# System.net
KiCad netlist of a schematic drawn in Altium Designer
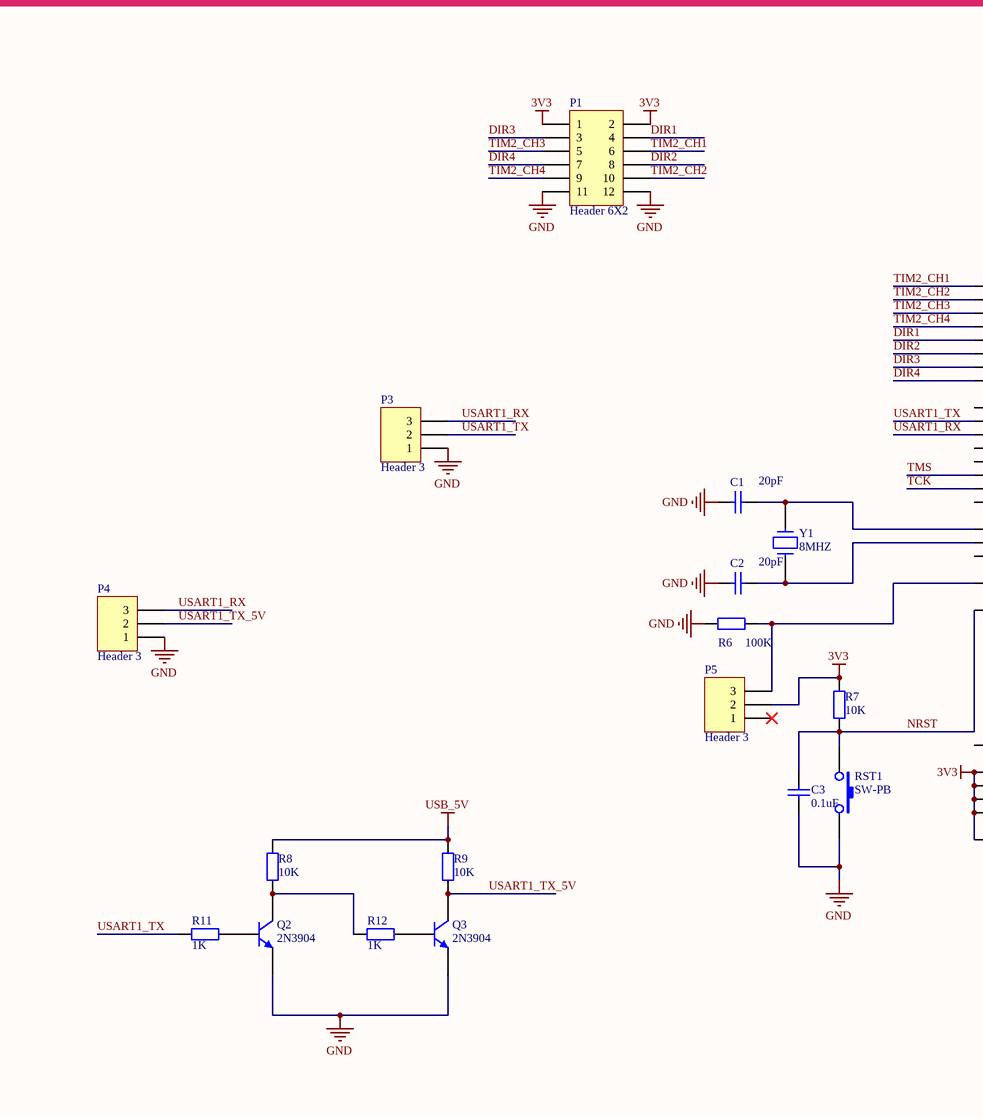
[diagram p0: System.SchDoc, left]
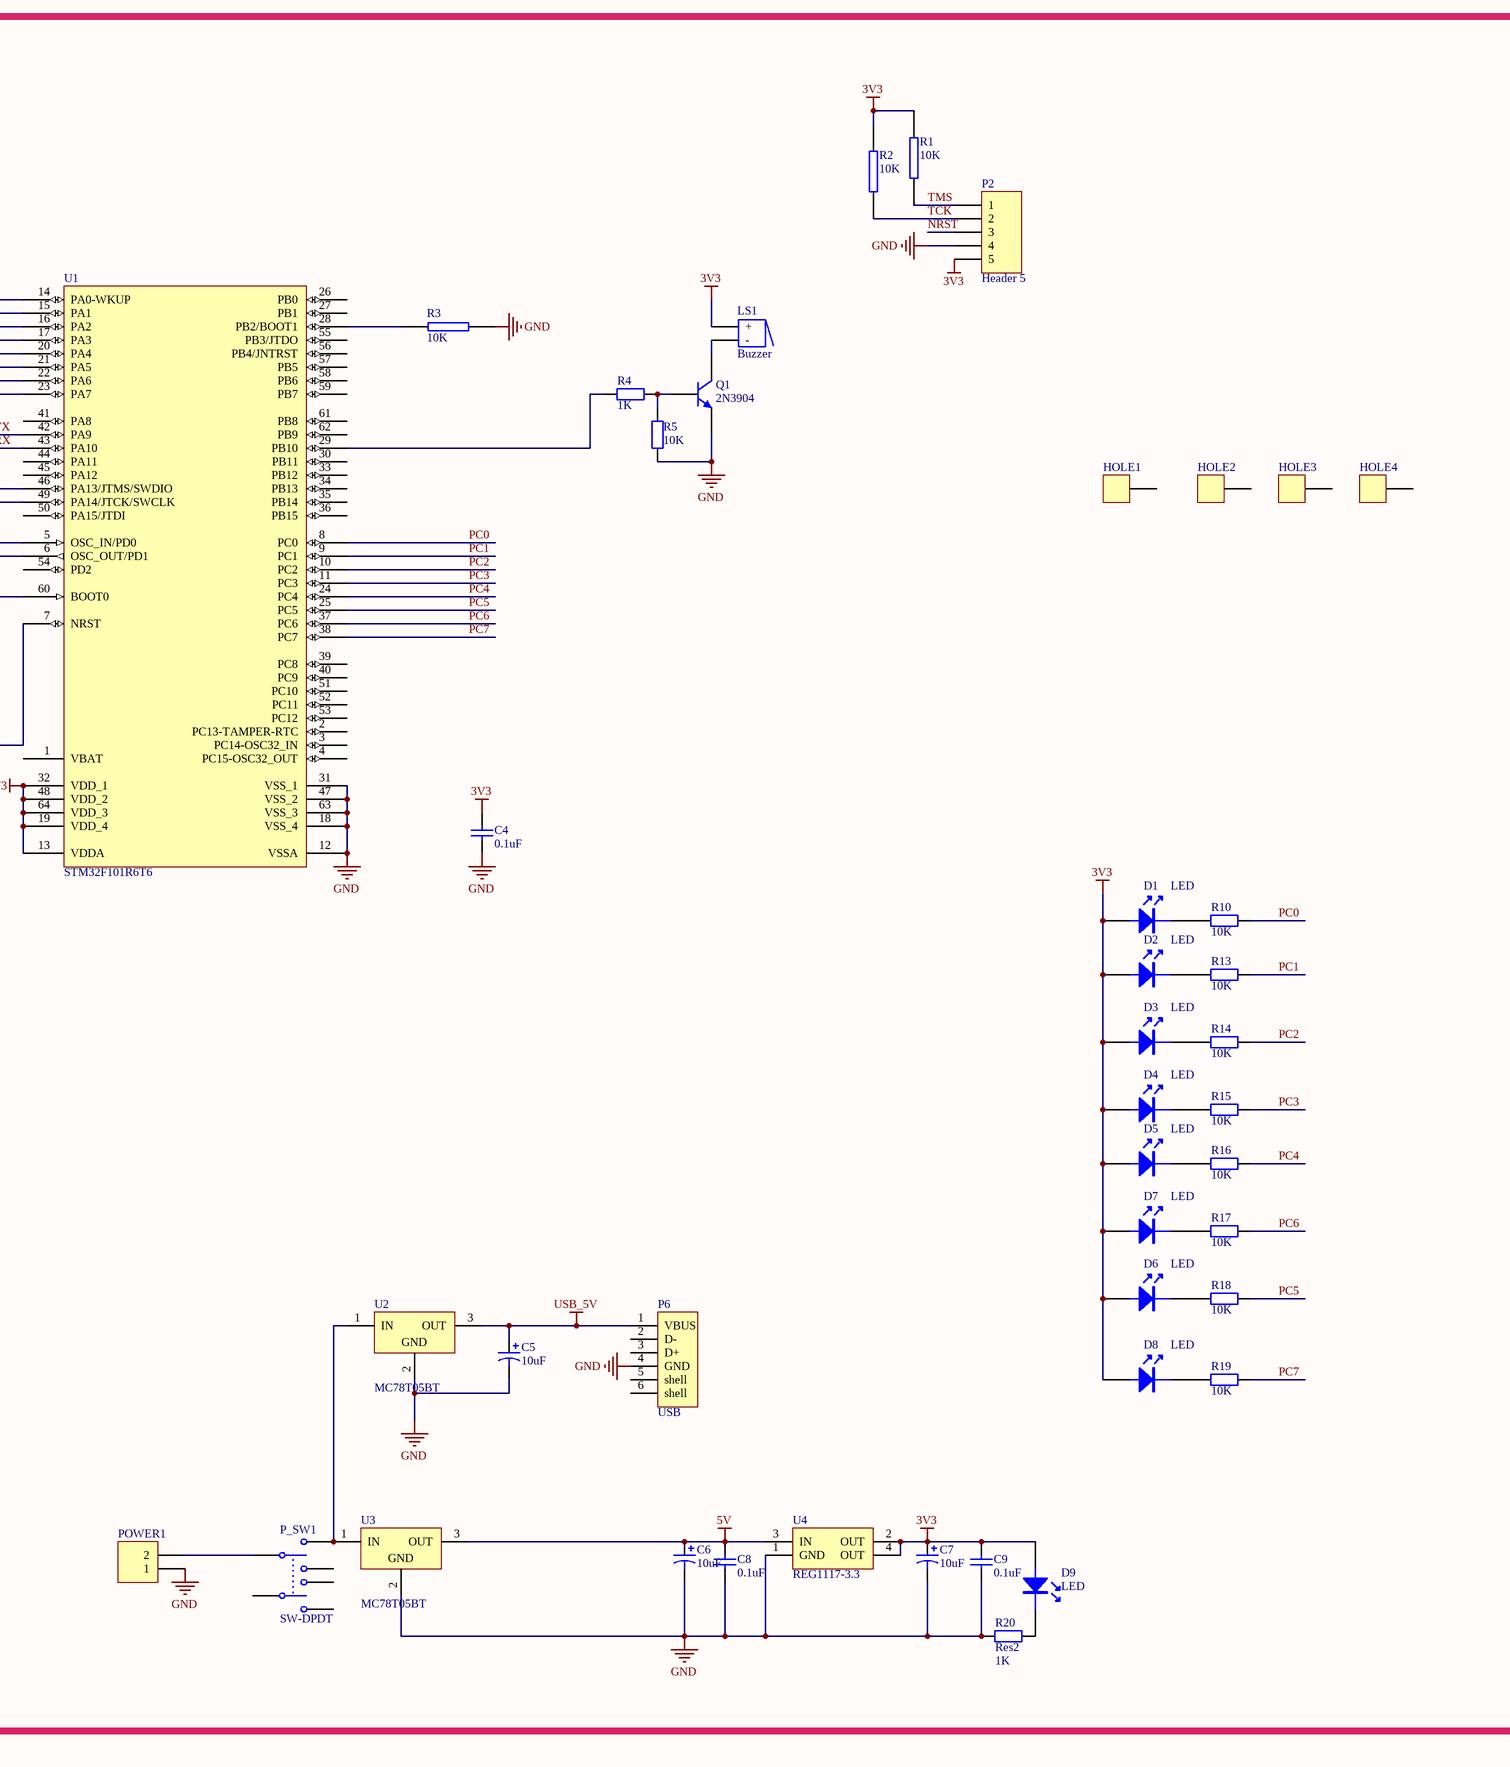
[diagram p1: System.SchDoc, right]

(export (version "E")
  (design (tool "Eeschema 10.0.6"))
  (components
    (comp (ref "C1")
      (value "20pF")
      (footprint "SMDC0805")
      (description "Capacitor")
      (fields (field (name "Comment") "Cap") (field (name "PUBLISHER") "Altium Limited"))
      (libsource (lib "Miscellaneous Devices") (part "Cap"))
    )
    (comp (ref "C2")
      (value "20pF")
      (footprint "SMDC0805")
      (description "Capacitor")
      (fields (field (name "Comment") "Cap") (field (name "PUBLISHER") "Altium Limited"))
      (libsource (lib "Miscellaneous Devices") (part "Cap"))
    )
    (comp (ref "C3")
      (value "0.1uF")
      (footprint "SMDC0805")
      (description "Capacitor")
      (fields (field (name "Comment") "Cap") (field (name "PUBLISHER") "Altium Limited"))
      (libsource (lib "Miscellaneous Devices") (part "Cap"))
    )
    (comp (ref "C4")
      (value "0.1uF")
      (footprint "SMDC0805")
      (description "Capacitor")
      (fields (field (name "Comment") "Cap") (field (name "PUBLISHER") "Altium Limited"))
      (libsource (lib "Miscellaneous Devices") (part "Cap"))
    )
    (comp (ref "C5")
      (value "10uF")
      (footprint "SMDT_C")
      (description "Polarized Capacitor (Radial)")
      (fields (field (name "Comment") "Cap Pol1") (field (name "PUBLISHER") "Altium Limited"))
      (libsource (lib "Miscellaneous Devices") (part "Cap Pol1"))
    )
    (comp (ref "C6")
      (value "10uF")
      (footprint "SMDT_C")
      (description "Polarized Capacitor (Radial)")
      (fields (field (name "Comment") "Cap Pol1") (field (name "PUBLISHER") "Altium Limited"))
      (libsource (lib "Miscellaneous Devices") (part "Cap Pol1"))
    )
    (comp (ref "C7")
      (value "10uF")
      (footprint "SMDT_C")
      (description "Polarized Capacitor (Radial)")
      (fields (field (name "Comment") "Cap Pol1") (field (name "PUBLISHER") "Altium Limited"))
      (libsource (lib "Miscellaneous Devices") (part "Cap Pol1"))
    )
    (comp (ref "C8")
      (value "0.1uF")
      (footprint "SMDC0805")
      (description "Capacitor")
      (fields (field (name "Comment") "Cap") (field (name "PUBLISHER") "Altium Limited"))
      (libsource (lib "Miscellaneous Devices") (part "Cap"))
    )
    (comp (ref "C9")
      (value "0.1uF")
      (footprint "SMDC0805")
      (description "Capacitor")
      (fields (field (name "Comment") "Cap") (field (name "PUBLISHER") "Altium Limited"))
      (libsource (lib "Miscellaneous Devices") (part "Cap"))
    )
    (comp (ref "D1") (value "LED") (footprint "LED_0805") (libsource (lib "library") (part "LED")))
    (comp (ref "D2") (value "LED") (footprint "LED_0805") (libsource (lib "library") (part "LED")))
    (comp (ref "D3") (value "LED") (footprint "LED_0805") (libsource (lib "library") (part "LED")))
    (comp (ref "D4") (value "LED") (footprint "LED_0805") (libsource (lib "library") (part "LED")))
    (comp (ref "D5") (value "LED") (footprint "LED_0805") (libsource (lib "library") (part "LED")))
    (comp (ref "D6") (value "LED") (footprint "LED_0805") (libsource (lib "library") (part "LED")))
    (comp (ref "D7") (value "LED") (footprint "LED_0805") (libsource (lib "library") (part "LED")))
    (comp (ref "D8") (value "LED") (footprint "LED_0805") (libsource (lib "library") (part "LED")))
    (comp (ref "D9") (value "LED") (footprint "LED_0805") (libsource (lib "library") (part "LED")))
    (comp (ref "HOLE1") (value "TP") (footprint "HOLE") (libsource (lib "library") (part "TestPoint")))
    (comp (ref "HOLE2") (value "TP") (footprint "HOLE") (libsource (lib "library") (part "TestPoint")))
    (comp (ref "HOLE3") (value "TP") (footprint "HOLE") (libsource (lib "library") (part "TestPoint")))
    (comp (ref "HOLE4") (value "TP") (footprint "HOLE") (libsource (lib "library") (part "TestPoint")))
    (comp (ref "LS1")
      (value "Buzzer")
      (footprint "Buzzer_min")
      (description "Magnetic Transducer Buzzer")
      (fields (field (name "PUBLISHER") "Altium Limited"))
      (libsource (lib "library") (part "Buzzer"))
    )
    (comp (ref "P1")
      (value "Header 6X2")
      (footprint "HDR2X6")
      (description "Header, 6-Pin, Dual row")
      (fields (field (name "PUBLISHER") "Altium Limited"))
      (libsource (lib "Miscellaneous Connectors") (part "Header 6X2"))
    )
    (comp (ref "P2")
      (value "Header 5")
      (footprint "HDR1X5")
      (description "Header, 5-Pin")
      (fields (field (name "PUBLISHER") "Altium Limited"))
      (libsource (lib "Miscellaneous Connectors") (part "Header 5"))
    )
    (comp (ref "P3")
      (value "Header 3")
      (footprint "HDR1X3")
      (description "Header, 3-Pin")
      (fields (field (name "PUBLISHER") "Altium Limited"))
      (libsource (lib "Miscellaneous Connectors") (part "Header 3"))
    )
    (comp (ref "P4")
      (value "Header 3")
      (footprint "HDR1X3")
      (description "Header, 3-Pin")
      (fields (field (name "PUBLISHER") "Altium Limited"))
      (libsource (lib "Miscellaneous Connectors") (part "Header 3"))
    )
    (comp (ref "P5")
      (value "Header 3")
      (footprint "HDR1X3")
      (description "Header, 3-Pin")
      (fields (field (name "PUBLISHER") "Altium Limited"))
      (libsource (lib "Miscellaneous Connectors") (part "Header 3"))
    )
    (comp (ref "P6") (value "USB") (footprint "USB-A") (libsource (lib "Lib") (part "USB")))
    (comp (ref "POWER1")
      (value "Header 2")
      (footprint "POW")
      (description "Header, 2-Pin")
      (fields (field (name "PUBLISHER") "Altium Limited"))
      (libsource (lib "Miscellaneous Connectors") (part "Header 2"))
    )
    (comp (ref "P_SW1")
      (value "SW-DPDT")
      (footprint "PW-S")
      (description "Double-Pole, Double-Throw Switch")
      (fields (field (name "PUBLISHER") "Altium Limited"))
      (libsource (lib "Miscellaneous Devices") (part "SW-DPDT"))
    )
    (comp (ref "Q1")
      (value "2N3904")
      (footprint "SOT23")
      (description "NPN General Purpose Amplifier")
      (fields (field (name "PUBLISHER") "Altium Limited"))
      (libsource (lib "library") (part "2N3904"))
    )
    (comp (ref "Q2")
      (value "2N3904")
      (footprint "SOT23")
      (description "NPN General Purpose Amplifier")
      (fields (field (name "PUBLISHER") "Altium Limited"))
      (libsource (lib "library") (part "2N3904"))
    )
    (comp (ref "Q3")
      (value "2N3904")
      (footprint "SOT23")
      (description "NPN General Purpose Amplifier")
      (fields (field (name "PUBLISHER") "Altium Limited"))
      (libsource (lib "library") (part "2N3904"))
    )
    (comp (ref "R1") (value "10K") (footprint "SMDR0805") (libsource (lib "*") (part "RES2")))
    (comp (ref "R2") (value "10K") (footprint "SMDR0805") (libsource (lib "*") (part "RES2")))
    (comp (ref "R3") (value "10K") (footprint "SMDR0805") (libsource (lib "*") (part "RES2")))
    (comp (ref "R4")
      (value "1K")
      (footprint "SMDR0805")
      (description "Resistor")
      (fields (field (name "Comment") "Res2") (field (name "PUBLISHER") "Altium Limited"))
      (libsource (lib "Miscellaneous Devices") (part "Res2"))
    )
    (comp (ref "R5")
      (value "10K")
      (footprint "SMDR0805")
      (description "Resistor")
      (fields (field (name "Comment") "Res2") (field (name "PUBLISHER") "Altium Limited"))
      (libsource (lib "") (part "Res2_2"))
    )
    (comp (ref "R6")
      (value "100K")
      (footprint "SMDR0805")
      (description "Resistor")
      (fields (field (name "Comment") "Res2") (field (name "PUBLISHER") "Altium Limited"))
      (libsource (lib "") (part "Res2_2"))
    )
    (comp (ref "R7")
      (value "10K")
      (footprint "SMDR0805")
      (description "Resistor")
      (fields (field (name "Comment") "Res2") (field (name "PUBLISHER") "Altium Limited"))
      (libsource (lib "Miscellaneous Devices") (part "Res2"))
    )
    (comp (ref "R8")
      (value "10K")
      (footprint "SMDR0805")
      (description "Resistor")
      (fields (field (name "Comment") "Res2") (field (name "PUBLISHER") "Altium Limited"))
      (libsource (lib "") (part "Res2_2"))
    )
    (comp (ref "R9")
      (value "10K")
      (footprint "SMDR0805")
      (description "Resistor")
      (fields (field (name "Comment") "Res2") (field (name "PUBLISHER") "Altium Limited"))
      (libsource (lib "") (part "Res2_2"))
    )
    (comp (ref "R10")
      (value "10K")
      (footprint "SMDR0805")
      (description "Resistor")
      (fields (field (name "Comment") "Res2") (field (name "PUBLISHER") "Altium Limited"))
      (libsource (lib "") (part "Res2_1"))
    )
    (comp (ref "R11")
      (value "1K")
      (footprint "SMDR0805")
      (description "Resistor")
      (fields (field (name "Comment") "Res2") (field (name "PUBLISHER") "Altium Limited"))
      (libsource (lib "Miscellaneous Devices") (part "Res2"))
    )
    (comp (ref "R12")
      (value "1K")
      (footprint "SMDR0805")
      (description "Resistor")
      (fields (field (name "Comment") "Res2") (field (name "PUBLISHER") "Altium Limited"))
      (libsource (lib "Miscellaneous Devices") (part "Res2"))
    )
    (comp (ref "R13")
      (value "10K")
      (footprint "SMDR0805")
      (description "Resistor")
      (fields (field (name "Comment") "Res2") (field (name "PUBLISHER") "Altium Limited"))
      (libsource (lib "") (part "Res2_1"))
    )
    (comp (ref "R14")
      (value "10K")
      (footprint "SMDR0805")
      (description "Resistor")
      (fields (field (name "Comment") "Res2") (field (name "PUBLISHER") "Altium Limited"))
      (libsource (lib "") (part "Res2_1"))
    )
    (comp (ref "R15")
      (value "10K")
      (footprint "SMDR0805")
      (description "Resistor")
      (fields (field (name "Comment") "Res2") (field (name "PUBLISHER") "Altium Limited"))
      (libsource (lib "") (part "Res2_1"))
    )
    (comp (ref "R16")
      (value "10K")
      (footprint "SMDR0805")
      (description "Resistor")
      (fields (field (name "Comment") "Res2") (field (name "PUBLISHER") "Altium Limited"))
      (libsource (lib "") (part "Res2_1"))
    )
    (comp (ref "R17")
      (value "10K")
      (footprint "SMDR0805")
      (description "Resistor")
      (fields (field (name "Comment") "Res2") (field (name "PUBLISHER") "Altium Limited"))
      (libsource (lib "") (part "Res2_1"))
    )
    (comp (ref "R18")
      (value "10K")
      (footprint "SMDR0805")
      (description "Resistor")
      (fields (field (name "Comment") "Res2") (field (name "PUBLISHER") "Altium Limited"))
      (libsource (lib "") (part "Res2_1"))
    )
    (comp (ref "R19")
      (value "10K")
      (footprint "SMDR0805")
      (description "Resistor")
      (fields (field (name "Comment") "Res2") (field (name "PUBLISHER") "Altium Limited"))
      (libsource (lib "") (part "Res2_1"))
    )
    (comp (ref "R20")
      (value "Res2")
      (footprint "SMDR0805")
      (description "Resistor")
      (fields (field (name "ALTIUM_VALUE") "1K") (field (name "PUBLISHER") "Altium Limited"))
      (libsource (lib "") (part "Res2_2"))
    )
    (comp (ref "RST1") (value "SW-PB") (footprint "key_2pin") (libsource (lib "library") (part "SW-PB")))
    (comp (ref "U1")
      (value "STM32F101R6T6")
      (footprint "LQFP64_M")
      (description "STM32 ARM-based 32-bit MCU with 32 Kbytes Flash, 64-pin LQFP, Industrial Temperature")
      (fields (field (name "PUBLISHER") "Altium Limited"))
      (libsource (lib "ST Microcontroller 32-Bit STM32") (part "STM32F101R6T6"))
    )
    (comp (ref "U2")
      (value "MC78T05BT")
      (footprint "MC78M05C")
      (description "Three-Ampere Positive Fixed Voltage Regulator")
      (fields (field (name "PUBLISHER") "Altium Limited"))
      (libsource (lib "Motorola Power Mgt Voltage Regulator") (part "MC78T05BT"))
    )
    (comp (ref "U3")
      (value "MC78T05BT")
      (footprint "MC78M05C")
      (description "Three-Ampere Positive Fixed Voltage Regulator")
      (fields (field (name "PUBLISHER") "Altium Limited"))
      (libsource (lib "Motorola Power Mgt Voltage Regulator") (part "MC78T05BT"))
    )
    (comp (ref "U4")
      (value "REG1117-3.3")
      (footprint "SOT-23")
      (description "800mA and 1A Low Dropout Positive Regulator 2.85V, 3.3V, 5V, and Adjustable")
      (fields (field (name "PUBLISHER") "*"))
      (libsource (lib "library") (part "REG1117-3.3"))
    )
    (comp (ref "Y1")
      (value "8MHZ")
      (footprint "可换晶振")
      (description "Crystal")
      (libsource (lib "library") (part "CRYSTAL"))
    )
  )
  (nets
    (net (code "1") (name "/DIR1") (class "Default")
      (node (ref "P1") (pin "4") (pinfunction "4_4") (pintype "passive"))
      (node (ref "U1") (pin "20") (pinfunction "PA4_20") (pintype "bidirectional"))
    )
    (net (code "2") (name "/DIR2") (class "Default")
      (node (ref "P1") (pin "8") (pinfunction "8_8") (pintype "passive"))
      (node (ref "U1") (pin "21") (pinfunction "PA5_21") (pintype "bidirectional"))
    )
    (net (code "3") (name "/DIR3") (class "Default")
      (node (ref "P1") (pin "3") (pinfunction "3_3") (pintype "passive"))
      (node (ref "U1") (pin "22") (pinfunction "PA6_22") (pintype "bidirectional"))
    )
    (net (code "4") (name "/DIR4") (class "Default")
      (node (ref "P1") (pin "7") (pinfunction "7_7") (pintype "passive"))
      (node (ref "U1") (pin "23") (pinfunction "PA7_23") (pintype "bidirectional"))
    )
    (net (code "5") (name "/NRST") (class "Default")
      (node (ref "C3") (pin "2") (pinfunction "2_2") (pintype "passive"))
      (node (ref "P2") (pin "3") (pinfunction "3_3") (pintype "passive"))
      (node (ref "R7") (pin "1") (pinfunction "1_1") (pintype "passive"))
      (node (ref "RST1") (pin "1") (pinfunction "1_1") (pintype "passive"))
      (node (ref "U1") (pin "7") (pinfunction "NRST_7") (pintype "bidirectional"))
    )
    (net (code "6") (name "/PC0") (class "Default")
      (node (ref "R10") (pin "1") (pinfunction "1_1") (pintype "passive"))
      (node (ref "U1") (pin "8") (pinfunction "PC0_8") (pintype "bidirectional"))
    )
    (net (code "7") (name "/PC1") (class "Default")
      (node (ref "R13") (pin "1") (pinfunction "1_1") (pintype "passive"))
      (node (ref "U1") (pin "9") (pinfunction "PC1_9") (pintype "bidirectional"))
    )
    (net (code "8") (name "/PC2") (class "Default")
      (node (ref "R14") (pin "1") (pinfunction "1_1") (pintype "passive"))
      (node (ref "U1") (pin "10") (pinfunction "PC2_10") (pintype "bidirectional"))
    )
    (net (code "9") (name "/PC3") (class "Default")
      (node (ref "R15") (pin "1") (pinfunction "1_1") (pintype "passive"))
      (node (ref "U1") (pin "11") (pinfunction "PC3_11") (pintype "bidirectional"))
    )
    (net (code "10") (name "/PC4") (class "Default")
      (node (ref "R16") (pin "1") (pinfunction "1_1") (pintype "passive"))
      (node (ref "U1") (pin "24") (pinfunction "PC4_24") (pintype "bidirectional"))
    )
    (net (code "11") (name "/PC5") (class "Default")
      (node (ref "R18") (pin "1") (pinfunction "1_1") (pintype "passive"))
      (node (ref "U1") (pin "25") (pinfunction "PC5_25") (pintype "bidirectional"))
    )
    (net (code "12") (name "/PC6") (class "Default")
      (node (ref "R17") (pin "1") (pinfunction "1_1") (pintype "passive"))
      (node (ref "U1") (pin "37") (pinfunction "PC6_37") (pintype "bidirectional"))
    )
    (net (code "13") (name "/PC7") (class "Default")
      (node (ref "R19") (pin "1") (pinfunction "1_1") (pintype "passive"))
      (node (ref "U1") (pin "38") (pinfunction "PC7_38") (pintype "bidirectional"))
    )
    (net (code "14") (name "/TCK") (class "Default")
      (node (ref "P2") (pin "2") (pinfunction "2_2") (pintype "passive"))
      (node (ref "R2") (pin "2") (pinfunction "2_2") (pintype "passive"))
      (node (ref "U1") (pin "49") (pinfunction "PA14/JTCK/SWCLK_49") (pintype "bidirectional"))
    )
    (net (code "15") (name "/TIM2_CH1") (class "Default")
      (node (ref "P1") (pin "6") (pinfunction "6_6") (pintype "passive"))
      (node (ref "U1") (pin "14") (pinfunction "PA0-WKUP_14") (pintype "bidirectional"))
    )
    (net (code "16") (name "/TIM2_CH2") (class "Default")
      (node (ref "P1") (pin "10") (pinfunction "10_10") (pintype "passive"))
      (node (ref "U1") (pin "15") (pinfunction "PA1_15") (pintype "bidirectional"))
    )
    (net (code "17") (name "/TIM2_CH3") (class "Default")
      (node (ref "P1") (pin "5") (pinfunction "5_5") (pintype "passive"))
      (node (ref "U1") (pin "16") (pinfunction "PA2_16") (pintype "bidirectional"))
    )
    (net (code "18") (name "/TIM2_CH4") (class "Default")
      (node (ref "P1") (pin "9") (pinfunction "9_9") (pintype "passive"))
      (node (ref "U1") (pin "17") (pinfunction "PA3_17") (pintype "bidirectional"))
    )
    (net (code "19") (name "/TMS") (class "Default")
      (node (ref "P2") (pin "1") (pinfunction "1_1") (pintype "passive"))
      (node (ref "R1") (pin "2") (pinfunction "2_2") (pintype "passive"))
      (node (ref "U1") (pin "46") (pinfunction "PA13/JTMS/SWDIO_46") (pintype "bidirectional"))
    )
    (net (code "20") (name "/USART1_RX") (class "Default")
      (node (ref "P3") (pin "3") (pinfunction "3_3") (pintype "passive"))
      (node (ref "P4") (pin "3") (pinfunction "3_3") (pintype "passive"))
      (node (ref "U1") (pin "43") (pinfunction "PA10_43") (pintype "bidirectional"))
    )
    (net (code "21") (name "/USART1_TX") (class "Default")
      (node (ref "P3") (pin "2") (pinfunction "2_2") (pintype "passive"))
      (node (ref "R11") (pin "1") (pinfunction "1_1") (pintype "passive"))
      (node (ref "U1") (pin "42") (pinfunction "PA9_42") (pintype "bidirectional"))
    )
    (net (code "22") (name "/USART1_TX_5V") (class "Default")
      (node (ref "P4") (pin "2") (pinfunction "2_2") (pintype "passive"))
      (node (ref "Q3") (pin "3") (pinfunction "C_3") (pintype "passive"))
      (node (ref "R9") (pin "1") (pinfunction "1_1") (pintype "passive"))
    )
    (net (code "23") (name "3V3") (class "Default")
      (node (ref "C4") (pin "2") (pinfunction "2_2") (pintype "passive"))
      (node (ref "C7") (pin "1") (pinfunction "1_1") (pintype "passive"))
      (node (ref "C9") (pin "2") (pinfunction "2_2") (pintype "passive"))
      (node (ref "D1") (pin "1") (pinfunction "A_1") (pintype "passive"))
      (node (ref "D2") (pin "1") (pinfunction "A_1") (pintype "passive"))
      (node (ref "D3") (pin "1") (pinfunction "A_1") (pintype "passive"))
      (node (ref "D4") (pin "1") (pinfunction "A_1") (pintype "passive"))
      (node (ref "D5") (pin "1") (pinfunction "A_1") (pintype "passive"))
      (node (ref "D6") (pin "1") (pinfunction "A_1") (pintype "passive"))
      (node (ref "D7") (pin "1") (pinfunction "A_1") (pintype "passive"))
      (node (ref "D8") (pin "1") (pinfunction "A_1") (pintype "passive"))
      (node (ref "D9") (pin "1") (pinfunction "A_1") (pintype "passive"))
      (node (ref "LS1") (pin "1") (pinfunction "+_1") (pintype "passive"))
      (node (ref "P1") (pin "1") (pinfunction "1_1") (pintype "passive"))
      (node (ref "P1") (pin "2") (pinfunction "2_2") (pintype "passive"))
      (node (ref "P2") (pin "5") (pinfunction "5_5") (pintype "passive"))
      (node (ref "P5") (pin "2") (pinfunction "2_2") (pintype "passive"))
      (node (ref "R1") (pin "1") (pinfunction "1_1") (pintype "passive"))
      (node (ref "R2") (pin "1") (pinfunction "1_1") (pintype "passive"))
      (node (ref "R7") (pin "2") (pinfunction "2_2") (pintype "passive"))
      (node (ref "U1") (pin "13") (pinfunction "VDDA_13") (pintype "power_in"))
      (node (ref "U1") (pin "19") (pinfunction "VDD_4_19") (pintype "power_in"))
      (node (ref "U1") (pin "32") (pinfunction "VDD_1_32") (pintype "power_in"))
      (node (ref "U1") (pin "48") (pinfunction "VDD_2_48") (pintype "power_in"))
      (node (ref "U1") (pin "64") (pinfunction "VDD_3_64") (pintype "power_in"))
      (node (ref "U4") (pin "2") (pinfunction "OUT_2") (pintype "power_in"))
      (node (ref "U4") (pin "4") (pinfunction "OUT_4") (pintype "power_in"))
    )
    (net (code "24") (name "5V") (class "Default")
      (node (ref "C6") (pin "1") (pinfunction "1_1") (pintype "passive"))
      (node (ref "C8") (pin "2") (pinfunction "2_2") (pintype "passive"))
      (node (ref "U3") (pin "3") (pinfunction "OUT_3") (pintype "power_in"))
      (node (ref "U4") (pin "3") (pinfunction "IN_3") (pintype "power_in"))
    )
    (net (code "25") (name "GND") (class "Default")
      (node (ref "C1") (pin "1") (pinfunction "1_1") (pintype "passive"))
      (node (ref "C2") (pin "1") (pinfunction "1_1") (pintype "passive"))
      (node (ref "C3") (pin "1") (pinfunction "1_1") (pintype "passive"))
      (node (ref "C4") (pin "1") (pinfunction "1_1") (pintype "passive"))
      (node (ref "C5") (pin "2") (pinfunction "2_2") (pintype "passive"))
      (node (ref "C6") (pin "2") (pinfunction "2_2") (pintype "passive"))
      (node (ref "C7") (pin "2") (pinfunction "2_2") (pintype "passive"))
      (node (ref "C8") (pin "1") (pinfunction "1_1") (pintype "passive"))
      (node (ref "C9") (pin "1") (pinfunction "1_1") (pintype "passive"))
      (node (ref "P1") (pin "11") (pinfunction "11_11") (pintype "passive"))
      (node (ref "P1") (pin "12") (pinfunction "12_12") (pintype "passive"))
      (node (ref "P2") (pin "4") (pinfunction "4_4") (pintype "passive"))
      (node (ref "P3") (pin "1") (pinfunction "1_1") (pintype "passive"))
      (node (ref "P4") (pin "1") (pinfunction "1_1") (pintype "passive"))
      (node (ref "P6") (pin "4") (pinfunction "GND_4") (pintype "passive"))
      (node (ref "POWER1") (pin "1") (pinfunction "1_1") (pintype "passive"))
      (node (ref "Q1") (pin "2") (pinfunction "E_2") (pintype "passive"))
      (node (ref "Q2") (pin "2") (pinfunction "E_2") (pintype "passive"))
      (node (ref "Q3") (pin "2") (pinfunction "E_2") (pintype "passive"))
      (node (ref "R20") (pin "1") (pinfunction "1_1") (pintype "passive"))
      (node (ref "R3") (pin "2") (pinfunction "2_2") (pintype "passive"))
      (node (ref "R5") (pin "1") (pinfunction "1_1") (pintype "passive"))
      (node (ref "R6") (pin "1") (pinfunction "1_1") (pintype "passive"))
      (node (ref "RST1") (pin "2") (pinfunction "2_2") (pintype "passive"))
      (node (ref "U1") (pin "12") (pinfunction "VSSA_12") (pintype "power_in"))
      (node (ref "U1") (pin "18") (pinfunction "VSS_4_18") (pintype "power_in"))
      (node (ref "U1") (pin "31") (pinfunction "VSS_1_31") (pintype "power_in"))
      (node (ref "U1") (pin "47") (pinfunction "VSS_2_47") (pintype "power_in"))
      (node (ref "U1") (pin "63") (pinfunction "VSS_3_63") (pintype "power_in"))
      (node (ref "U2") (pin "2") (pinfunction "GND_2") (pintype "power_in"))
      (node (ref "U3") (pin "2") (pinfunction "GND_2") (pintype "power_in"))
      (node (ref "U4") (pin "1") (pinfunction "GND_1") (pintype "power_in"))
    )
    (net (code "26") (name "Net-(D1-K)") (class "Default")
      (node (ref "D1") (pin "2") (pinfunction "K_2") (pintype "passive"))
      (node (ref "R10") (pin "2") (pinfunction "2_2") (pintype "passive"))
    )
    (net (code "27") (name "Net-(D2-K)") (class "Default")
      (node (ref "D2") (pin "2") (pinfunction "K_2") (pintype "passive"))
      (node (ref "R13") (pin "2") (pinfunction "2_2") (pintype "passive"))
    )
    (net (code "28") (name "Net-(D3-K)") (class "Default")
      (node (ref "D3") (pin "2") (pinfunction "K_2") (pintype "passive"))
      (node (ref "R14") (pin "2") (pinfunction "2_2") (pintype "passive"))
    )
    (net (code "29") (name "Net-(D4-K)") (class "Default")
      (node (ref "D4") (pin "2") (pinfunction "K_2") (pintype "passive"))
      (node (ref "R15") (pin "2") (pinfunction "2_2") (pintype "passive"))
    )
    (net (code "30") (name "Net-(D5-K)") (class "Default")
      (node (ref "D5") (pin "2") (pinfunction "K_2") (pintype "passive"))
      (node (ref "R16") (pin "2") (pinfunction "2_2") (pintype "passive"))
    )
    (net (code "31") (name "Net-(D6-K)") (class "Default")
      (node (ref "D6") (pin "2") (pinfunction "K_2") (pintype "passive"))
      (node (ref "R18") (pin "2") (pinfunction "2_2") (pintype "passive"))
    )
    (net (code "32") (name "Net-(D7-K)") (class "Default")
      (node (ref "D7") (pin "2") (pinfunction "K_2") (pintype "passive"))
      (node (ref "R17") (pin "2") (pinfunction "2_2") (pintype "passive"))
    )
    (net (code "33") (name "Net-(D8-K)") (class "Default")
      (node (ref "D8") (pin "2") (pinfunction "K_2") (pintype "passive"))
      (node (ref "R19") (pin "2") (pinfunction "2_2") (pintype "passive"))
    )
    (net (code "34") (name "Net-(D9-K)") (class "Default")
      (node (ref "D9") (pin "2") (pinfunction "K_2") (pintype "passive"))
      (node (ref "R20") (pin "2") (pinfunction "2_2") (pintype "passive"))
    )
    (net (code "35") (name "Net-(LS1--)") (class "Default")
      (node (ref "LS1") (pin "2") (pinfunction "-_2") (pintype "passive"))
      (node (ref "Q1") (pin "3") (pinfunction "C_3") (pintype "passive"))
    )
    (net (code "36") (name "Net-(POWER1-Pad2)") (class "Default")
      (node (ref "POWER1") (pin "2") (pinfunction "2_2") (pintype "passive"))
      (node (ref "P_SW1") (pin "1") (pinfunction "1_1") (pintype "passive"))
    )
    (net (code "37") (name "Net-(Q1-B)") (class "Default")
      (node (ref "Q1") (pin "1") (pinfunction "B_1") (pintype "passive"))
      (node (ref "R4") (pin "2") (pinfunction "2_2") (pintype "passive"))
      (node (ref "R5") (pin "2") (pinfunction "2_2") (pintype "passive"))
    )
    (net (code "38") (name "Net-(Q2-B)") (class "Default")
      (node (ref "Q2") (pin "1") (pinfunction "B_1") (pintype "passive"))
      (node (ref "R11") (pin "2") (pinfunction "2_2") (pintype "passive"))
    )
    (net (code "39") (name "Net-(Q2-C)") (class "Default")
      (node (ref "Q2") (pin "3") (pinfunction "C_3") (pintype "passive"))
      (node (ref "R12") (pin "1") (pinfunction "1_1") (pintype "passive"))
      (node (ref "R8") (pin "1") (pinfunction "1_1") (pintype "passive"))
    )
    (net (code "40") (name "Net-(Q3-B)") (class "Default")
      (node (ref "Q3") (pin "1") (pinfunction "B_1") (pintype "passive"))
      (node (ref "R12") (pin "2") (pinfunction "2_2") (pintype "passive"))
    )
    (net (code "41") (name "Net-(U1-BOOT0)") (class "Default")
      (node (ref "P5") (pin "3") (pinfunction "3_3") (pintype "passive"))
      (node (ref "R6") (pin "2") (pinfunction "2_2") (pintype "passive"))
      (node (ref "U1") (pin "60") (pinfunction "BOOT0_60") (pintype "input"))
    )
    (net (code "42") (name "Net-(U1-OSC_IN{slash}PD0)") (class "Default")
      (node (ref "C1") (pin "2") (pinfunction "2_2") (pintype "passive"))
      (node (ref "U1") (pin "5") (pinfunction "OSC_IN/PD0_5") (pintype "input"))
      (node (ref "Y1") (pin "2") (pinfunction "2_2") (pintype "passive"))
    )
    (net (code "43") (name "Net-(U1-OSC_OUT{slash}PD1)") (class "Default")
      (node (ref "C2") (pin "2") (pinfunction "2_2") (pintype "passive"))
      (node (ref "U1") (pin "6") (pinfunction "OSC_OUT/PD1_6") (pintype "output"))
      (node (ref "Y1") (pin "1") (pinfunction "1_1") (pintype "passive"))
    )
    (net (code "44") (name "Net-(U1-PB2{slash}BOOT1)") (class "Default")
      (node (ref "R3") (pin "1") (pinfunction "1_1") (pintype "passive"))
      (node (ref "U1") (pin "28") (pinfunction "PB2/BOOT1_28") (pintype "bidirectional"))
    )
    (net (code "45") (name "Net-(U1-PB10)") (class "Default")
      (node (ref "R4") (pin "1") (pinfunction "1_1") (pintype "passive"))
      (node (ref "U1") (pin "29") (pinfunction "PB10_29") (pintype "bidirectional"))
    )
    (net (code "46") (name "Net-(U2-IN)") (class "Default")
      (node (ref "P_SW1") (pin "2") (pinfunction "2_2") (pintype "passive"))
      (node (ref "U2") (pin "1") (pinfunction "IN_1") (pintype "power_in"))
      (node (ref "U3") (pin "1") (pinfunction "IN_1") (pintype "power_in"))
    )
    (net (code "47") (name "USB_5V") (class "Default")
      (node (ref "C5") (pin "1") (pinfunction "1_1") (pintype "passive"))
      (node (ref "P6") (pin "1") (pinfunction "VBUS_1") (pintype "passive"))
      (node (ref "R8") (pin "2") (pinfunction "2_2") (pintype "passive"))
      (node (ref "R9") (pin "2") (pinfunction "2_2") (pintype "passive"))
      (node (ref "U2") (pin "3") (pinfunction "OUT_3") (pintype "power_in"))
    )
    (net (code "48") (name "unconnected-(HOLE1-A-Pad1)") (class "Default")
      (node (ref "HOLE1") (pin "1") (pinfunction "A_1") (pintype "passive"))
    )
    (net (code "49") (name "unconnected-(HOLE2-A-Pad1)") (class "Default")
      (node (ref "HOLE2") (pin "1") (pinfunction "A_1") (pintype "passive"))
    )
    (net (code "50") (name "unconnected-(HOLE3-A-Pad1)") (class "Default")
      (node (ref "HOLE3") (pin "1") (pinfunction "A_1") (pintype "passive"))
    )
    (net (code "51") (name "unconnected-(HOLE4-A-Pad1)") (class "Default")
      (node (ref "HOLE4") (pin "1") (pinfunction "A_1") (pintype "passive"))
    )
    (net (code "52") (name "unconnected-(P5-Pad1)") (class "Default")
      (node (ref "P5") (pin "1") (pinfunction "1_1") (pintype "passive+no_connect"))
    )
    (net (code "53") (name "unconnected-(P6-D+-Pad3)") (class "Default")
      (node (ref "P6") (pin "3") (pinfunction "D+_3") (pintype "passive"))
    )
    (net (code "54") (name "unconnected-(P6-D--Pad2)") (class "Default")
      (node (ref "P6") (pin "2") (pinfunction "D-_2") (pintype "passive"))
    )
    (net (code "55") (name "unconnected-(P6-shell-Pad5)") (class "Default")
      (node (ref "P6") (pin "5") (pinfunction "shell_5") (pintype "passive"))
    )
    (net (code "56") (name "unconnected-(P6-shell-Pad6)") (class "Default")
      (node (ref "P6") (pin "6") (pinfunction "shell_6") (pintype "passive"))
    )
    (net (code "57") (name "unconnected-(P_SW1-Pad3)") (class "Default")
      (node (ref "P_SW1") (pin "3") (pinfunction "3_3") (pintype "passive"))
    )
    (net (code "58") (name "unconnected-(P_SW1-Pad4)") (class "Default")
      (node (ref "P_SW1") (pin "4") (pinfunction "4_4") (pintype "passive"))
    )
    (net (code "59") (name "unconnected-(P_SW1-Pad5)") (class "Default")
      (node (ref "P_SW1") (pin "5") (pinfunction "5_5") (pintype "passive"))
    )
    (net (code "60") (name "unconnected-(P_SW1-Pad6)") (class "Default")
      (node (ref "P_SW1") (pin "6") (pinfunction "6_6") (pintype "passive"))
    )
    (net (code "61") (name "unconnected-(U1-PA8-Pad41)") (class "Default")
      (node (ref "U1") (pin "41") (pinfunction "PA8_41") (pintype "bidirectional"))
    )
    (net (code "62") (name "unconnected-(U1-PA11-Pad44)") (class "Default")
      (node (ref "U1") (pin "44") (pinfunction "PA11_44") (pintype "bidirectional"))
    )
    (net (code "63") (name "unconnected-(U1-PA12-Pad45)") (class "Default")
      (node (ref "U1") (pin "45") (pinfunction "PA12_45") (pintype "bidirectional"))
    )
    (net (code "64") (name "unconnected-(U1-PA15{slash}JTDI-Pad50)") (class "Default")
      (node (ref "U1") (pin "50") (pinfunction "PA15/JTDI_50") (pintype "bidirectional"))
    )
    (net (code "65") (name "unconnected-(U1-PB0-Pad26)") (class "Default")
      (node (ref "U1") (pin "26") (pinfunction "PB0_26") (pintype "bidirectional"))
    )
    (net (code "66") (name "unconnected-(U1-PB1-Pad27)") (class "Default")
      (node (ref "U1") (pin "27") (pinfunction "PB1_27") (pintype "bidirectional"))
    )
    (net (code "67") (name "unconnected-(U1-PB3{slash}JTDO-Pad55)") (class "Default")
      (node (ref "U1") (pin "55") (pinfunction "PB3/JTDO_55") (pintype "bidirectional"))
    )
    (net (code "68") (name "unconnected-(U1-PB4{slash}JNTRST-Pad56)") (class "Default")
      (node (ref "U1") (pin "56") (pinfunction "PB4/JNTRST_56") (pintype "bidirectional"))
    )
    (net (code "69") (name "unconnected-(U1-PB5-Pad57)") (class "Default")
      (node (ref "U1") (pin "57") (pinfunction "PB5_57") (pintype "bidirectional"))
    )
    (net (code "70") (name "unconnected-(U1-PB6-Pad58)") (class "Default")
      (node (ref "U1") (pin "58") (pinfunction "PB6_58") (pintype "bidirectional"))
    )
    (net (code "71") (name "unconnected-(U1-PB7-Pad59)") (class "Default")
      (node (ref "U1") (pin "59") (pinfunction "PB7_59") (pintype "bidirectional"))
    )
    (net (code "72") (name "unconnected-(U1-PB8-Pad61)") (class "Default")
      (node (ref "U1") (pin "61") (pinfunction "PB8_61") (pintype "bidirectional"))
    )
    (net (code "73") (name "unconnected-(U1-PB9-Pad62)") (class "Default")
      (node (ref "U1") (pin "62") (pinfunction "PB9_62") (pintype "bidirectional"))
    )
    (net (code "74") (name "unconnected-(U1-PB11-Pad30)") (class "Default")
      (node (ref "U1") (pin "30") (pinfunction "PB11_30") (pintype "bidirectional"))
    )
    (net (code "75") (name "unconnected-(U1-PB12-Pad33)") (class "Default")
      (node (ref "U1") (pin "33") (pinfunction "PB12_33") (pintype "bidirectional"))
    )
    (net (code "76") (name "unconnected-(U1-PB13-Pad34)") (class "Default")
      (node (ref "U1") (pin "34") (pinfunction "PB13_34") (pintype "bidirectional"))
    )
    (net (code "77") (name "unconnected-(U1-PB14-Pad35)") (class "Default")
      (node (ref "U1") (pin "35") (pinfunction "PB14_35") (pintype "bidirectional"))
    )
    (net (code "78") (name "unconnected-(U1-PB15-Pad36)") (class "Default")
      (node (ref "U1") (pin "36") (pinfunction "PB15_36") (pintype "bidirectional"))
    )
    (net (code "79") (name "unconnected-(U1-PC8-Pad39)") (class "Default")
      (node (ref "U1") (pin "39") (pinfunction "PC8_39") (pintype "bidirectional"))
    )
    (net (code "80") (name "unconnected-(U1-PC9-Pad40)") (class "Default")
      (node (ref "U1") (pin "40") (pinfunction "PC9_40") (pintype "bidirectional"))
    )
    (net (code "81") (name "unconnected-(U1-PC10-Pad51)") (class "Default")
      (node (ref "U1") (pin "51") (pinfunction "PC10_51") (pintype "bidirectional"))
    )
    (net (code "82") (name "unconnected-(U1-PC11-Pad52)") (class "Default")
      (node (ref "U1") (pin "52") (pinfunction "PC11_52") (pintype "bidirectional"))
    )
    (net (code "83") (name "unconnected-(U1-PC12-Pad53)") (class "Default")
      (node (ref "U1") (pin "53") (pinfunction "PC12_53") (pintype "bidirectional"))
    )
    (net (code "84") (name "unconnected-(U1-PC13-TAMPER-RTC-Pad2)") (class "Default")
      (node (ref "U1") (pin "2") (pinfunction "PC13-TAMPER-RTC_2") (pintype "bidirectional"))
    )
    (net (code "85") (name "unconnected-(U1-PC14-OSC32_IN-Pad3)") (class "Default")
      (node (ref "U1") (pin "3") (pinfunction "PC14-OSC32_IN_3") (pintype "bidirectional"))
    )
    (net (code "86") (name "unconnected-(U1-PC15-OSC32_OUT-Pad4)") (class "Default")
      (node (ref "U1") (pin "4") (pinfunction "PC15-OSC32_OUT_4") (pintype "bidirectional"))
    )
    (net (code "87") (name "unconnected-(U1-PD2-Pad54)") (class "Default")
      (node (ref "U1") (pin "54") (pinfunction "PD2_54") (pintype "bidirectional"))
    )
    (net (code "88") (name "unconnected-(U1-VBAT-Pad1)") (class "Default")
      (node (ref "U1") (pin "1") (pinfunction "VBAT_1") (pintype "power_in"))
    )
  )
)
